# 12v_-_5v.net
KiCad netlist of a schematic drawn in EAGLE
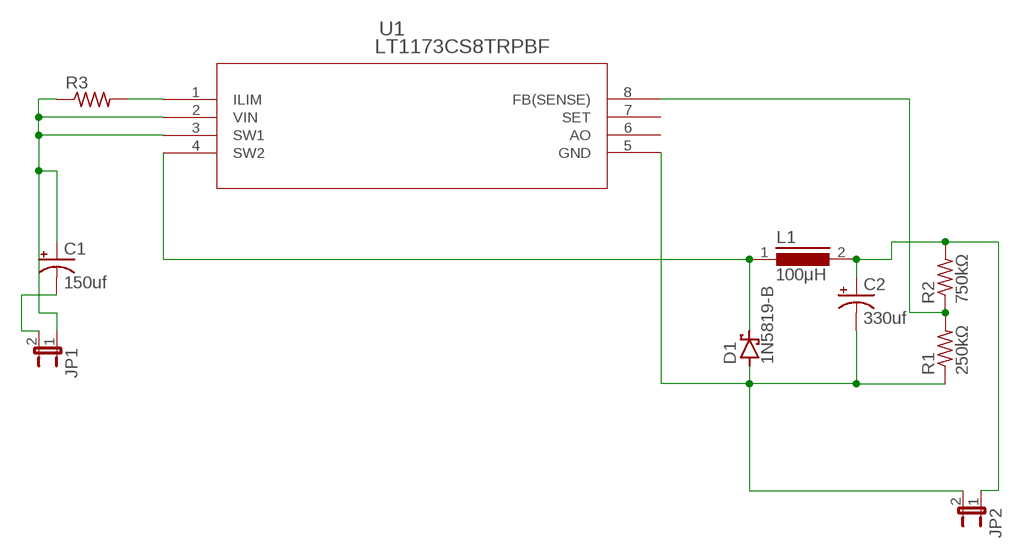
[diagram p0: schematic, sheet 1]

(export (version "E")
  (design (tool "Eeschema 10.0.6"))
  (components
    (comp (ref "C1")
      (value "150uf")
      (footprint "eagle-import:E2-5")
      (libsource (lib "eagle-import") (part "CPOL-USE2-5"))
    )
    (comp (ref "C2")
      (value "330uf")
      (footprint "eagle-import:E2-5")
      (libsource (lib "eagle-import") (part "CPOL-USE2-5"))
    )
    (comp (ref "D1")
      (value "1N5819-B")
      (footprint "eagle-import:DO41-7.6")
      (libsource (lib "eagle-import") (part "1N5819-B"))
    )
    (comp (ref "JP1")
      (value "JP1E")
      (footprint "eagle-import:JP1")
      (libsource (lib "eagle-import") (part "JP1E"))
    )
    (comp (ref "JP2")
      (value "JP1E")
      (footprint "eagle-import:JP1")
      (libsource (lib "eagle-import") (part "JP1E"))
    )
    (comp (ref "L1")
      (value "100μH")
      (footprint "eagle-import:S11-10")
      (libsource (lib "eagle-import") (part "R1003DS11"))
    )
    (comp (ref "R1")
      (value "250kΩ")
      (footprint "eagle-import:0204_7")
      (libsource (lib "eagle-import") (part "R-US_0204/7"))
    )
    (comp (ref "R2")
      (value "750kΩ")
      (footprint "eagle-import:0204_7")
      (libsource (lib "eagle-import") (part "R-US_0204/7"))
    )
    (comp (ref "R3")
      (value "R-US_0204/7")
      (footprint "eagle-import:0204_7")
      (libsource (lib "eagle-import") (part "R-US_0204/7"))
    )
    (comp (ref "U1")
      (value "LT1173CS8TRPBF")
      (footprint "eagle-import:SOIC-8_S")
      (fields
        (field (name "DIGI-KEY_PART_NUMBER") "LT1173CS8#TRPBF-ND")
        (field (name "MF") "Linear Technology/Analog")
        (field (name "MP") "LT1173CS8#TRPBF")
      )
      (libsource (lib "eagle-import") (part "LT1173CS8TRPBF"))
    )
  )
  (nets
    (net (code "1") (name "Net-(C1-Pad-)") (class "Default")
      (node (ref "C1") (pin "-") (pinfunction "-_-") (pintype "passive"))
      (node (ref "JP1") (pin "2") (pinfunction "2_2") (pintype "passive"))
    )
    (net (code "2") (name "Net-(C2-Pad+)") (class "Default")
      (node (ref "C2") (pin "+") (pinfunction "+_+") (pintype "passive"))
      (node (ref "JP2") (pin "1") (pinfunction "1_1") (pintype "passive"))
      (node (ref "L1") (pin "2") (pinfunction "2_2") (pintype "passive"))
      (node (ref "R2") (pin "2") (pinfunction "2_2") (pintype "passive"))
    )
    (net (code "3") (name "Net-(U1-FB(SENSE))") (class "Default")
      (node (ref "R1") (pin "2") (pinfunction "2_2") (pintype "passive"))
      (node (ref "R2") (pin "1") (pinfunction "1_1") (pintype "passive"))
      (node (ref "U1") (pin "8") (pinfunction "FB(SENSE)_8") (pintype "bidirectional"))
    )
    (net (code "4") (name "Net-(U1-GND)") (class "Default")
      (node (ref "C2") (pin "-") (pinfunction "-_-") (pintype "passive"))
      (node (ref "D1") (pin "A") (pinfunction "A_A") (pintype "passive"))
      (node (ref "JP2") (pin "2") (pinfunction "2_2") (pintype "passive"))
      (node (ref "R1") (pin "1") (pinfunction "1_1") (pintype "passive"))
      (node (ref "U1") (pin "5") (pinfunction "GND_5") (pintype "power_in"))
    )
    (net (code "5") (name "Net-(U1-ILIM)") (class "Default")
      (node (ref "R3") (pin "2") (pinfunction "2_2") (pintype "passive"))
      (node (ref "U1") (pin "1") (pinfunction "ILIM_1") (pintype "passive"))
    )
    (net (code "6") (name "Net-(U1-SW1)") (class "Default")
      (node (ref "C1") (pin "+") (pinfunction "+_+") (pintype "passive"))
      (node (ref "JP1") (pin "1") (pinfunction "1_1") (pintype "passive"))
      (node (ref "R3") (pin "1") (pinfunction "1_1") (pintype "passive"))
      (node (ref "U1") (pin "2") (pinfunction "VIN_2") (pintype "input"))
      (node (ref "U1") (pin "3") (pinfunction "SW1_3") (pintype "passive"))
    )
    (net (code "7") (name "Net-(U1-SW2)") (class "Default")
      (node (ref "D1") (pin "C") (pinfunction "C_C") (pintype "passive"))
      (node (ref "L1") (pin "1") (pinfunction "1_1") (pintype "passive"))
      (node (ref "U1") (pin "4") (pinfunction "SW2_4") (pintype "passive"))
    )
    (net (code "8") (name "unconnected-(U1-AO-Pad6)") (class "Default")
      (node (ref "U1") (pin "6") (pinfunction "AO_6") (pintype "output"))
    )
    (net (code "9") (name "unconnected-(U1-SET-Pad7)") (class "Default")
      (node (ref "U1") (pin "7") (pinfunction "SET_7") (pintype "input"))
    )
  )
)
